# breakout-ledpca9956b.net
KiCad netlist of a schematic drawn in EAGLE
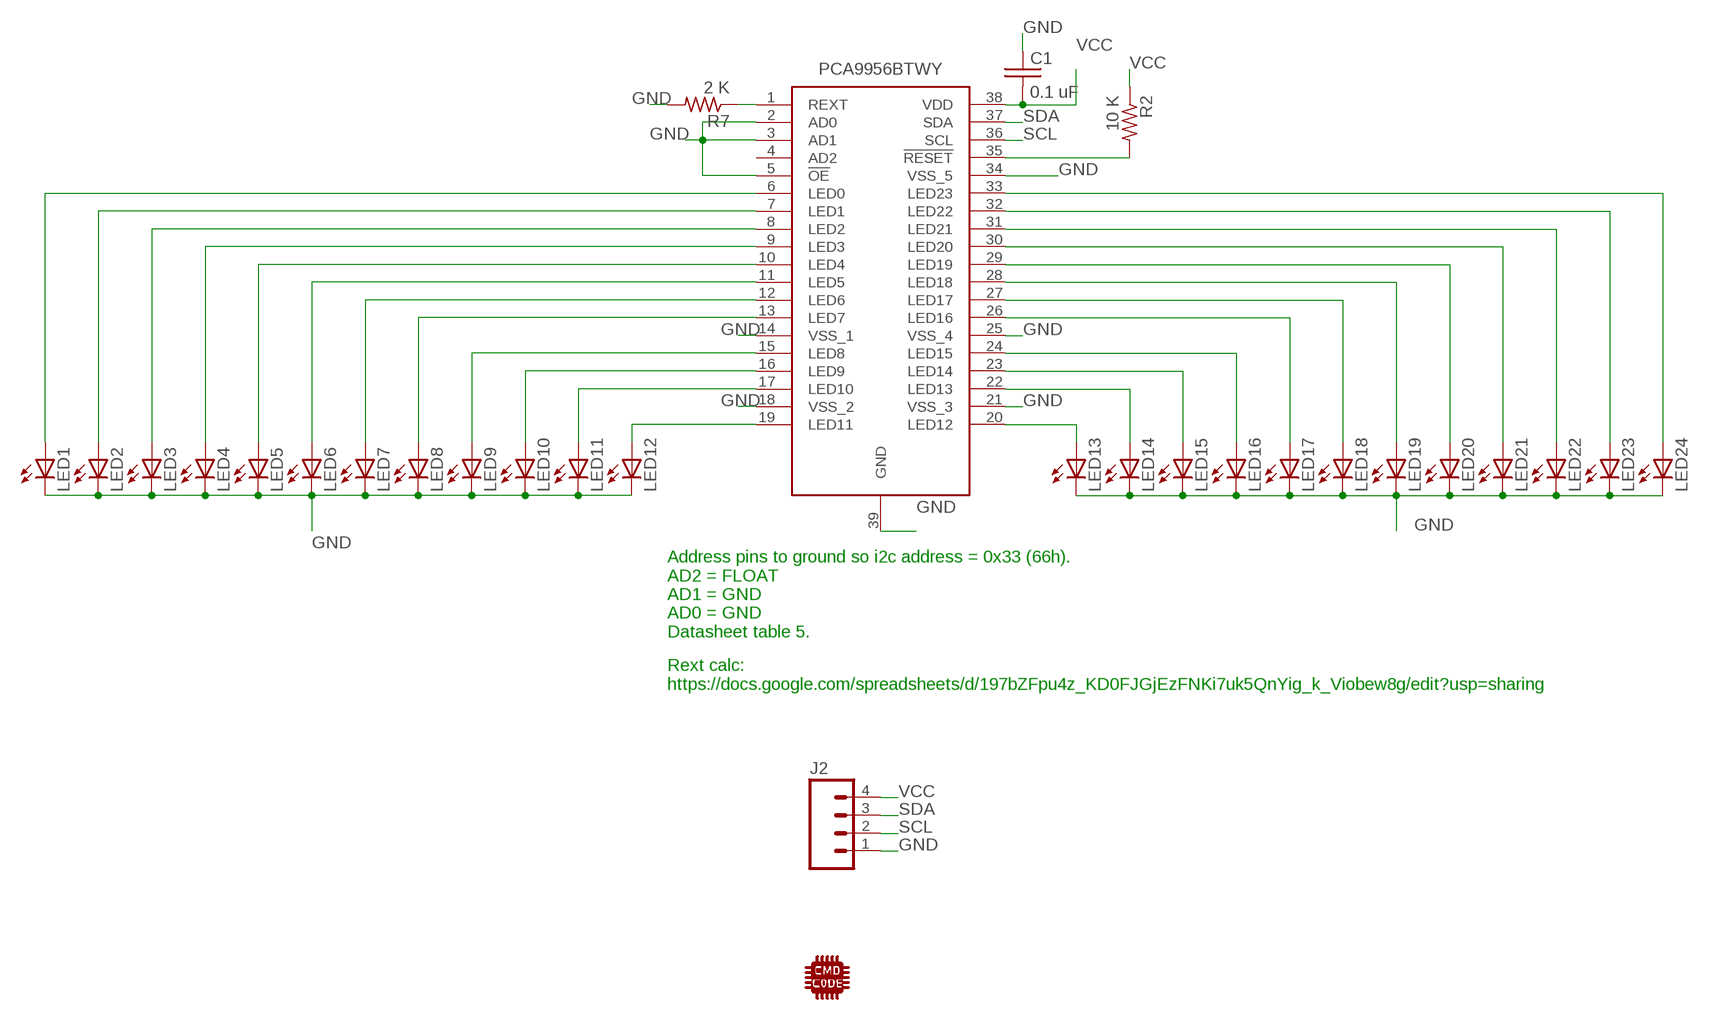
[diagram p0: schematic, sheet 1]

(export (version "E")
  (design (tool "Eeschema 10.0.6"))
  (components
    (comp (ref "C1")
      (value "0.1 uF")
      (footprint "eagle-import:C0805")
      (libsource (lib "eagle-import") (part "C-USC0805"))
    )
    (comp (ref "IC1")
      (value "PCA9956BTWY")
      (footprint "eagle-import:SOP50P640X110-39N")
      (fields (field (name "MOUSER_PART_NUMBER") "771-PCA9956BTWY"))
      (libsource (lib "eagle-import") (part "PCA9956BTWY"))
    )
    (comp (ref "J2")
      (value "M04PTH")
      (footprint "eagle-import:1X04")
      (libsource (lib "eagle-import") (part "M04PTH"))
    )
    (comp (ref "LED1")
      (value "LEDREVERSEMOUNT")
      (footprint "eagle-import:GULLWING_LED")
      (libsource (lib "eagle-import") (part "LEDREVERSEMOUNT"))
    )
    (comp (ref "LED2")
      (value "LEDREVERSEMOUNT")
      (footprint "eagle-import:GULLWING_LED")
      (libsource (lib "eagle-import") (part "LEDREVERSEMOUNT"))
    )
    (comp (ref "LED3")
      (value "LEDREVERSEMOUNT")
      (footprint "eagle-import:GULLWING_LED")
      (libsource (lib "eagle-import") (part "LEDREVERSEMOUNT"))
    )
    (comp (ref "LED4")
      (value "LEDREVERSEMOUNT")
      (footprint "eagle-import:GULLWING_LED")
      (libsource (lib "eagle-import") (part "LEDREVERSEMOUNT"))
    )
    (comp (ref "LED5")
      (value "LEDREVERSEMOUNT")
      (footprint "eagle-import:GULLWING_LED")
      (libsource (lib "eagle-import") (part "LEDREVERSEMOUNT"))
    )
    (comp (ref "LED6")
      (value "LEDREVERSEMOUNT")
      (footprint "eagle-import:GULLWING_LED")
      (libsource (lib "eagle-import") (part "LEDREVERSEMOUNT"))
    )
    (comp (ref "LED7")
      (value "LEDREVERSEMOUNT")
      (footprint "eagle-import:GULLWING_LED")
      (libsource (lib "eagle-import") (part "LEDREVERSEMOUNT"))
    )
    (comp (ref "LED8")
      (value "LEDREVERSEMOUNT")
      (footprint "eagle-import:GULLWING_LED")
      (libsource (lib "eagle-import") (part "LEDREVERSEMOUNT"))
    )
    (comp (ref "LED9")
      (value "LEDREVERSEMOUNT")
      (footprint "eagle-import:GULLWING_LED")
      (libsource (lib "eagle-import") (part "LEDREVERSEMOUNT"))
    )
    (comp (ref "LED10")
      (value "LEDREVERSEMOUNT")
      (footprint "eagle-import:GULLWING_LED")
      (libsource (lib "eagle-import") (part "LEDREVERSEMOUNT"))
    )
    (comp (ref "LED11")
      (value "LEDREVERSEMOUNT")
      (footprint "eagle-import:GULLWING_LED")
      (libsource (lib "eagle-import") (part "LEDREVERSEMOUNT"))
    )
    (comp (ref "LED12")
      (value "LEDREVERSEMOUNT")
      (footprint "eagle-import:GULLWING_LED")
      (libsource (lib "eagle-import") (part "LEDREVERSEMOUNT"))
    )
    (comp (ref "LED13")
      (value "LEDREVERSEMOUNT")
      (footprint "eagle-import:GULLWING_LED")
      (libsource (lib "eagle-import") (part "LEDREVERSEMOUNT"))
    )
    (comp (ref "LED14")
      (value "LEDREVERSEMOUNT")
      (footprint "eagle-import:GULLWING_LED")
      (libsource (lib "eagle-import") (part "LEDREVERSEMOUNT"))
    )
    (comp (ref "LED15")
      (value "LEDREVERSEMOUNT")
      (footprint "eagle-import:GULLWING_LED")
      (libsource (lib "eagle-import") (part "LEDREVERSEMOUNT"))
    )
    (comp (ref "LED16")
      (value "LEDREVERSEMOUNT")
      (footprint "eagle-import:GULLWING_LED")
      (libsource (lib "eagle-import") (part "LEDREVERSEMOUNT"))
    )
    (comp (ref "LED17")
      (value "LEDREVERSEMOUNT")
      (footprint "eagle-import:GULLWING_LED")
      (libsource (lib "eagle-import") (part "LEDREVERSEMOUNT"))
    )
    (comp (ref "LED18")
      (value "LEDREVERSEMOUNT")
      (footprint "eagle-import:GULLWING_LED")
      (libsource (lib "eagle-import") (part "LEDREVERSEMOUNT"))
    )
    (comp (ref "LED19")
      (value "LEDREVERSEMOUNT")
      (footprint "eagle-import:GULLWING_LED")
      (libsource (lib "eagle-import") (part "LEDREVERSEMOUNT"))
    )
    (comp (ref "LED20")
      (value "LEDREVERSEMOUNT")
      (footprint "eagle-import:GULLWING_LED")
      (libsource (lib "eagle-import") (part "LEDREVERSEMOUNT"))
    )
    (comp (ref "LED21")
      (value "LEDREVERSEMOUNT")
      (footprint "eagle-import:GULLWING_LED")
      (libsource (lib "eagle-import") (part "LEDREVERSEMOUNT"))
    )
    (comp (ref "LED22")
      (value "LEDREVERSEMOUNT")
      (footprint "eagle-import:GULLWING_LED")
      (libsource (lib "eagle-import") (part "LEDREVERSEMOUNT"))
    )
    (comp (ref "LED23")
      (value "LEDREVERSEMOUNT")
      (footprint "eagle-import:GULLWING_LED")
      (libsource (lib "eagle-import") (part "LEDREVERSEMOUNT"))
    )
    (comp (ref "LED24")
      (value "LEDREVERSEMOUNT")
      (footprint "eagle-import:GULLWING_LED")
      (libsource (lib "eagle-import") (part "LEDREVERSEMOUNT"))
    )
    (comp (ref "R2")
      (value "10 K")
      (footprint "eagle-import:R0805")
      (libsource (lib "eagle-import") (part "R-US_R0805"))
    )
    (comp (ref "R7")
      (value "2 K")
      (footprint "eagle-import:R0805")
      (libsource (lib "eagle-import") (part "R-US_R0805"))
    )
    (comp (ref "U$2")
      (value "CMD_C0DE_LOGO")
      (footprint "eagle-import:CMD_C0DE_LOGO")
      (libsource (lib "eagle-import") (part "CMD_C0DE_LOGO"))
    )
  )
  (nets
    (net (code "1") (name "/GND") (class "Default")
      (node (ref "C1") (pin "1") (pinfunction "1_1") (pintype "passive"))
      (node (ref "IC1") (pin "14") (pinfunction "VSS_1_14") (pintype "bidirectional"))
      (node (ref "IC1") (pin "18") (pinfunction "VSS_2_18") (pintype "bidirectional"))
      (node (ref "IC1") (pin "2") (pinfunction "AD0_2") (pintype "bidirectional"))
      (node (ref "IC1") (pin "21") (pinfunction "VSS_3_21") (pintype "bidirectional"))
      (node (ref "IC1") (pin "25") (pinfunction "VSS_4_25") (pintype "bidirectional"))
      (node (ref "IC1") (pin "3") (pinfunction "AD1_3") (pintype "bidirectional"))
      (node (ref "IC1") (pin "34") (pinfunction "VSS_5_34") (pintype "bidirectional"))
      (node (ref "IC1") (pin "39") (pinfunction "GND_39") (pintype "bidirectional"))
      (node (ref "IC1") (pin "5") (pinfunction "~{OE}_5") (pintype "bidirectional"))
      (node (ref "J2") (pin "1") (pinfunction "1_1") (pintype "passive"))
      (node (ref "LED1") (pin "C") (pinfunction "C_C") (pintype "output"))
      (node (ref "LED10") (pin "C") (pinfunction "C_C") (pintype "output"))
      (node (ref "LED11") (pin "C") (pinfunction "C_C") (pintype "output"))
      (node (ref "LED12") (pin "C") (pinfunction "C_C") (pintype "output"))
      (node (ref "LED13") (pin "C") (pinfunction "C_C") (pintype "output"))
      (node (ref "LED14") (pin "C") (pinfunction "C_C") (pintype "output"))
      (node (ref "LED15") (pin "C") (pinfunction "C_C") (pintype "output"))
      (node (ref "LED16") (pin "C") (pinfunction "C_C") (pintype "output"))
      (node (ref "LED17") (pin "C") (pinfunction "C_C") (pintype "output"))
      (node (ref "LED18") (pin "C") (pinfunction "C_C") (pintype "output"))
      (node (ref "LED19") (pin "C") (pinfunction "C_C") (pintype "output"))
      (node (ref "LED2") (pin "C") (pinfunction "C_C") (pintype "output"))
      (node (ref "LED20") (pin "C") (pinfunction "C_C") (pintype "output"))
      (node (ref "LED21") (pin "C") (pinfunction "C_C") (pintype "output"))
      (node (ref "LED22") (pin "C") (pinfunction "C_C") (pintype "output"))
      (node (ref "LED23") (pin "C") (pinfunction "C_C") (pintype "output"))
      (node (ref "LED24") (pin "C") (pinfunction "C_C") (pintype "output"))
      (node (ref "LED3") (pin "C") (pinfunction "C_C") (pintype "output"))
      (node (ref "LED4") (pin "C") (pinfunction "C_C") (pintype "output"))
      (node (ref "LED5") (pin "C") (pinfunction "C_C") (pintype "output"))
      (node (ref "LED6") (pin "C") (pinfunction "C_C") (pintype "output"))
      (node (ref "LED7") (pin "C") (pinfunction "C_C") (pintype "output"))
      (node (ref "LED8") (pin "C") (pinfunction "C_C") (pintype "output"))
      (node (ref "LED9") (pin "C") (pinfunction "C_C") (pintype "output"))
      (node (ref "R7") (pin "2") (pinfunction "2_2") (pintype "passive"))
    )
    (net (code "2") (name "/SCL") (class "Default")
      (node (ref "IC1") (pin "36") (pinfunction "SCL_36") (pintype "bidirectional"))
      (node (ref "J2") (pin "2") (pinfunction "2_2") (pintype "passive"))
    )
    (net (code "3") (name "/SDA") (class "Default")
      (node (ref "IC1") (pin "37") (pinfunction "SDA_37") (pintype "bidirectional"))
      (node (ref "J2") (pin "3") (pinfunction "3_3") (pintype "passive"))
    )
    (net (code "4") (name "/VCC") (class "Default")
      (node (ref "C1") (pin "2") (pinfunction "2_2") (pintype "passive"))
      (node (ref "IC1") (pin "38") (pinfunction "VDD_38") (pintype "bidirectional"))
      (node (ref "J2") (pin "4") (pinfunction "4_4") (pintype "passive"))
      (node (ref "R2") (pin "1") (pinfunction "1_1") (pintype "passive"))
    )
    (net (code "5") (name "Net-(IC1-LED0)") (class "Default")
      (node (ref "IC1") (pin "6") (pinfunction "LED0_6") (pintype "bidirectional"))
      (node (ref "LED1") (pin "A") (pinfunction "A_A") (pintype "input"))
    )
    (net (code "6") (name "Net-(IC1-LED1)") (class "Default")
      (node (ref "IC1") (pin "7") (pinfunction "LED1_7") (pintype "bidirectional"))
      (node (ref "LED2") (pin "A") (pinfunction "A_A") (pintype "input"))
    )
    (net (code "7") (name "Net-(IC1-LED2)") (class "Default")
      (node (ref "IC1") (pin "8") (pinfunction "LED2_8") (pintype "bidirectional"))
      (node (ref "LED3") (pin "A") (pinfunction "A_A") (pintype "input"))
    )
    (net (code "8") (name "Net-(IC1-LED3)") (class "Default")
      (node (ref "IC1") (pin "9") (pinfunction "LED3_9") (pintype "bidirectional"))
      (node (ref "LED4") (pin "A") (pinfunction "A_A") (pintype "input"))
    )
    (net (code "9") (name "Net-(IC1-LED4)") (class "Default")
      (node (ref "IC1") (pin "10") (pinfunction "LED4_10") (pintype "bidirectional"))
      (node (ref "LED5") (pin "A") (pinfunction "A_A") (pintype "input"))
    )
    (net (code "10") (name "Net-(IC1-LED5)") (class "Default")
      (node (ref "IC1") (pin "11") (pinfunction "LED5_11") (pintype "bidirectional"))
      (node (ref "LED6") (pin "A") (pinfunction "A_A") (pintype "input"))
    )
    (net (code "11") (name "Net-(IC1-LED6)") (class "Default")
      (node (ref "IC1") (pin "12") (pinfunction "LED6_12") (pintype "bidirectional"))
      (node (ref "LED7") (pin "A") (pinfunction "A_A") (pintype "input"))
    )
    (net (code "12") (name "Net-(IC1-LED7)") (class "Default")
      (node (ref "IC1") (pin "13") (pinfunction "LED7_13") (pintype "bidirectional"))
      (node (ref "LED8") (pin "A") (pinfunction "A_A") (pintype "input"))
    )
    (net (code "13") (name "Net-(IC1-LED8)") (class "Default")
      (node (ref "IC1") (pin "15") (pinfunction "LED8_15") (pintype "bidirectional"))
      (node (ref "LED9") (pin "A") (pinfunction "A_A") (pintype "input"))
    )
    (net (code "14") (name "Net-(IC1-LED9)") (class "Default")
      (node (ref "IC1") (pin "16") (pinfunction "LED9_16") (pintype "bidirectional"))
      (node (ref "LED10") (pin "A") (pinfunction "A_A") (pintype "input"))
    )
    (net (code "15") (name "Net-(IC1-LED10)") (class "Default")
      (node (ref "IC1") (pin "17") (pinfunction "LED10_17") (pintype "bidirectional"))
      (node (ref "LED11") (pin "A") (pinfunction "A_A") (pintype "input"))
    )
    (net (code "16") (name "Net-(IC1-LED11)") (class "Default")
      (node (ref "IC1") (pin "19") (pinfunction "LED11_19") (pintype "bidirectional"))
      (node (ref "LED12") (pin "A") (pinfunction "A_A") (pintype "input"))
    )
    (net (code "17") (name "Net-(IC1-LED12)") (class "Default")
      (node (ref "IC1") (pin "20") (pinfunction "LED12_20") (pintype "bidirectional"))
      (node (ref "LED13") (pin "A") (pinfunction "A_A") (pintype "input"))
    )
    (net (code "18") (name "Net-(IC1-LED13)") (class "Default")
      (node (ref "IC1") (pin "22") (pinfunction "LED13_22") (pintype "bidirectional"))
      (node (ref "LED14") (pin "A") (pinfunction "A_A") (pintype "input"))
    )
    (net (code "19") (name "Net-(IC1-LED14)") (class "Default")
      (node (ref "IC1") (pin "23") (pinfunction "LED14_23") (pintype "bidirectional"))
      (node (ref "LED15") (pin "A") (pinfunction "A_A") (pintype "input"))
    )
    (net (code "20") (name "Net-(IC1-LED15)") (class "Default")
      (node (ref "IC1") (pin "24") (pinfunction "LED15_24") (pintype "bidirectional"))
      (node (ref "LED16") (pin "A") (pinfunction "A_A") (pintype "input"))
    )
    (net (code "21") (name "Net-(IC1-LED16)") (class "Default")
      (node (ref "IC1") (pin "26") (pinfunction "LED16_26") (pintype "bidirectional"))
      (node (ref "LED17") (pin "A") (pinfunction "A_A") (pintype "input"))
    )
    (net (code "22") (name "Net-(IC1-LED17)") (class "Default")
      (node (ref "IC1") (pin "27") (pinfunction "LED17_27") (pintype "bidirectional"))
      (node (ref "LED18") (pin "A") (pinfunction "A_A") (pintype "input"))
    )
    (net (code "23") (name "Net-(IC1-LED18)") (class "Default")
      (node (ref "IC1") (pin "28") (pinfunction "LED18_28") (pintype "bidirectional"))
      (node (ref "LED19") (pin "A") (pinfunction "A_A") (pintype "input"))
    )
    (net (code "24") (name "Net-(IC1-LED19)") (class "Default")
      (node (ref "IC1") (pin "29") (pinfunction "LED19_29") (pintype "bidirectional"))
      (node (ref "LED20") (pin "A") (pinfunction "A_A") (pintype "input"))
    )
    (net (code "25") (name "Net-(IC1-LED20)") (class "Default")
      (node (ref "IC1") (pin "30") (pinfunction "LED20_30") (pintype "bidirectional"))
      (node (ref "LED21") (pin "A") (pinfunction "A_A") (pintype "input"))
    )
    (net (code "26") (name "Net-(IC1-LED21)") (class "Default")
      (node (ref "IC1") (pin "31") (pinfunction "LED21_31") (pintype "bidirectional"))
      (node (ref "LED22") (pin "A") (pinfunction "A_A") (pintype "input"))
    )
    (net (code "27") (name "Net-(IC1-LED22)") (class "Default")
      (node (ref "IC1") (pin "32") (pinfunction "LED22_32") (pintype "bidirectional"))
      (node (ref "LED23") (pin "A") (pinfunction "A_A") (pintype "input"))
    )
    (net (code "28") (name "Net-(IC1-LED23)") (class "Default")
      (node (ref "IC1") (pin "33") (pinfunction "LED23_33") (pintype "bidirectional"))
      (node (ref "LED24") (pin "A") (pinfunction "A_A") (pintype "input"))
    )
    (net (code "29") (name "Net-(IC1-REXT)") (class "Default")
      (node (ref "IC1") (pin "1") (pinfunction "REXT_1") (pintype "bidirectional"))
      (node (ref "R7") (pin "1") (pinfunction "1_1") (pintype "passive"))
    )
    (net (code "30") (name "Net-(IC1-~{RESET})") (class "Default")
      (node (ref "IC1") (pin "35") (pinfunction "~{RESET}_35") (pintype "bidirectional"))
      (node (ref "R2") (pin "2") (pinfunction "2_2") (pintype "passive"))
    )
    (net (code "31") (name "unconnected-(IC1-AD2-Pad4)") (class "Default")
      (node (ref "IC1") (pin "4") (pinfunction "AD2_4") (pintype "bidirectional"))
    )
  )
)
